# Jumper.net
KiCad netlist of a schematic drawn in Altium Designer
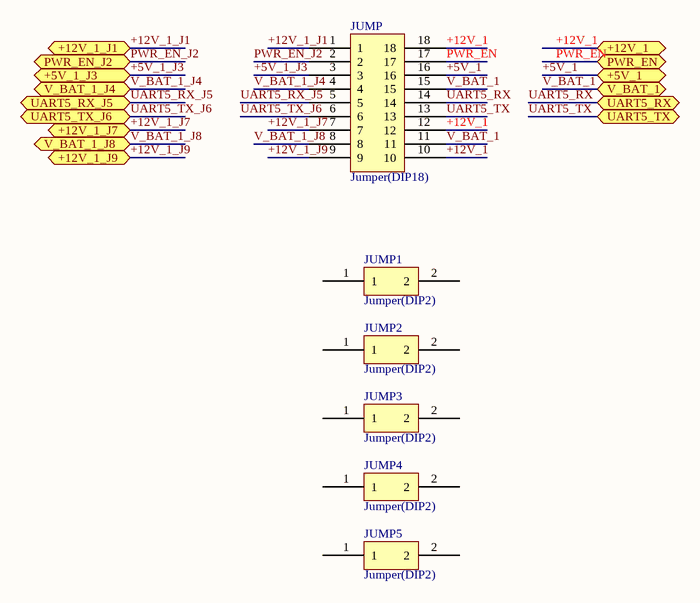
[diagram p0: Jumper.SchDoc]

(export (version "E")
  (design (tool "Eeschema 10.0.6"))
  (components
    (comp (ref "JUMP")
      (value "Jumper(DIP18)")
      (footprint "UmbilicalConnectors:Jumper(DIP18)")
      (libsource (lib "UmbilicalBoardV2") (part "Jumper(DIP18)"))
    )
    (comp (ref "JUMP1")
      (value "Jumper(DIP2)")
      (footprint "UmbilicalConnectors:Jumper(DIP2)")
      (libsource (lib "UmbilicalBoardV2") (part "Jumper(DIP2)"))
    )
    (comp (ref "JUMP2")
      (value "Jumper(DIP2)")
      (footprint "UmbilicalConnectors:Jumper(DIP2)")
      (libsource (lib "UmbilicalBoardV2") (part "Jumper(DIP2)"))
    )
    (comp (ref "JUMP3")
      (value "Jumper(DIP2)")
      (footprint "UmbilicalConnectors:Jumper(DIP2)")
      (libsource (lib "UmbilicalBoardV2") (part "Jumper(DIP2)"))
    )
    (comp (ref "JUMP4")
      (value "Jumper(DIP2)")
      (footprint "UmbilicalConnectors:Jumper(DIP2)")
      (libsource (lib "UmbilicalBoardV2") (part "Jumper(DIP2)"))
    )
    (comp (ref "JUMP5")
      (value "Jumper(DIP2)")
      (footprint "UmbilicalConnectors:Jumper(DIP2)")
      (libsource (lib "UmbilicalBoardV2") (part "Jumper(DIP2)"))
    )
  )
  (nets
    (net (code "1") (name "/+5V_1") (class "Default")
      (node (ref "JUMP") (pin "16") (pinfunction "16_16") (pintype "passive"))
    )
    (net (code "2") (name "/+5V_1_J3") (class "Default")
      (node (ref "JUMP") (pin "3") (pinfunction "3_3") (pintype "passive"))
    )
    (net (code "3") (name "/+12V_1") (class "Default")
      (node (ref "JUMP") (pin "10") (pinfunction "10_10") (pintype "passive"))
      (node (ref "JUMP") (pin "12") (pinfunction "12_12") (pintype "passive"))
      (node (ref "JUMP") (pin "18") (pinfunction "18_18") (pintype "passive"))
    )
    (net (code "4") (name "/+12V_1_J1") (class "Default")
      (node (ref "JUMP") (pin "1") (pinfunction "1_1") (pintype "passive"))
    )
    (net (code "5") (name "/+12V_1_J7") (class "Default")
      (node (ref "JUMP") (pin "7") (pinfunction "7_7") (pintype "passive"))
    )
    (net (code "6") (name "/+12V_1_J9") (class "Default")
      (node (ref "JUMP") (pin "9") (pinfunction "9_9") (pintype "passive"))
    )
    (net (code "7") (name "/PWR_EN") (class "Default")
      (node (ref "JUMP") (pin "17") (pinfunction "17_17") (pintype "passive"))
    )
    (net (code "8") (name "/PWR_EN_J2") (class "Default")
      (node (ref "JUMP") (pin "2") (pinfunction "2_2") (pintype "passive"))
    )
    (net (code "9") (name "/UART5_RX") (class "Default")
      (node (ref "JUMP") (pin "14") (pinfunction "14_14") (pintype "passive"))
    )
    (net (code "10") (name "/UART5_RX_J5") (class "Default")
      (node (ref "JUMP") (pin "5") (pinfunction "5_5") (pintype "passive"))
    )
    (net (code "11") (name "/UART5_TX") (class "Default")
      (node (ref "JUMP") (pin "13") (pinfunction "13_13") (pintype "passive"))
    )
    (net (code "12") (name "/UART5_TX_J6") (class "Default")
      (node (ref "JUMP") (pin "6") (pinfunction "6_6") (pintype "passive"))
    )
    (net (code "13") (name "/V_BAT_1") (class "Default")
      (node (ref "JUMP") (pin "11") (pinfunction "11_11") (pintype "passive"))
      (node (ref "JUMP") (pin "15") (pinfunction "15_15") (pintype "passive"))
    )
    (net (code "14") (name "/V_BAT_1_J4") (class "Default")
      (node (ref "JUMP") (pin "4") (pinfunction "4_4") (pintype "passive"))
    )
    (net (code "15") (name "/V_BAT_1_J8") (class "Default")
      (node (ref "JUMP") (pin "8") (pinfunction "8_8") (pintype "passive"))
    )
    (net (code "16") (name "unconnected-(JUMP1-Pad1)") (class "Default")
      (node (ref "JUMP1") (pin "1") (pinfunction "1_1") (pintype "passive"))
    )
    (net (code "17") (name "unconnected-(JUMP1-Pad2)") (class "Default")
      (node (ref "JUMP1") (pin "2") (pinfunction "2_2") (pintype "passive"))
    )
    (net (code "18") (name "unconnected-(JUMP2-Pad1)") (class "Default")
      (node (ref "JUMP2") (pin "1") (pinfunction "1_1") (pintype "passive"))
    )
    (net (code "19") (name "unconnected-(JUMP2-Pad2)") (class "Default")
      (node (ref "JUMP2") (pin "2") (pinfunction "2_2") (pintype "passive"))
    )
    (net (code "20") (name "unconnected-(JUMP3-Pad1)") (class "Default")
      (node (ref "JUMP3") (pin "1") (pinfunction "1_1") (pintype "passive"))
    )
    (net (code "21") (name "unconnected-(JUMP3-Pad2)") (class "Default")
      (node (ref "JUMP3") (pin "2") (pinfunction "2_2") (pintype "passive"))
    )
    (net (code "22") (name "unconnected-(JUMP4-Pad1)") (class "Default")
      (node (ref "JUMP4") (pin "1") (pinfunction "1_1") (pintype "passive"))
    )
    (net (code "23") (name "unconnected-(JUMP4-Pad2)") (class "Default")
      (node (ref "JUMP4") (pin "2") (pinfunction "2_2") (pintype "passive"))
    )
    (net (code "24") (name "unconnected-(JUMP5-Pad1)") (class "Default")
      (node (ref "JUMP5") (pin "1") (pinfunction "1_1") (pintype "passive"))
    )
    (net (code "25") (name "unconnected-(JUMP5-Pad2)") (class "Default")
      (node (ref "JUMP5") (pin "2") (pinfunction "2_2") (pintype "passive"))
    )
  )
)
